# ledpcb.net
KiCad netlist of a schematic drawn in EAGLE
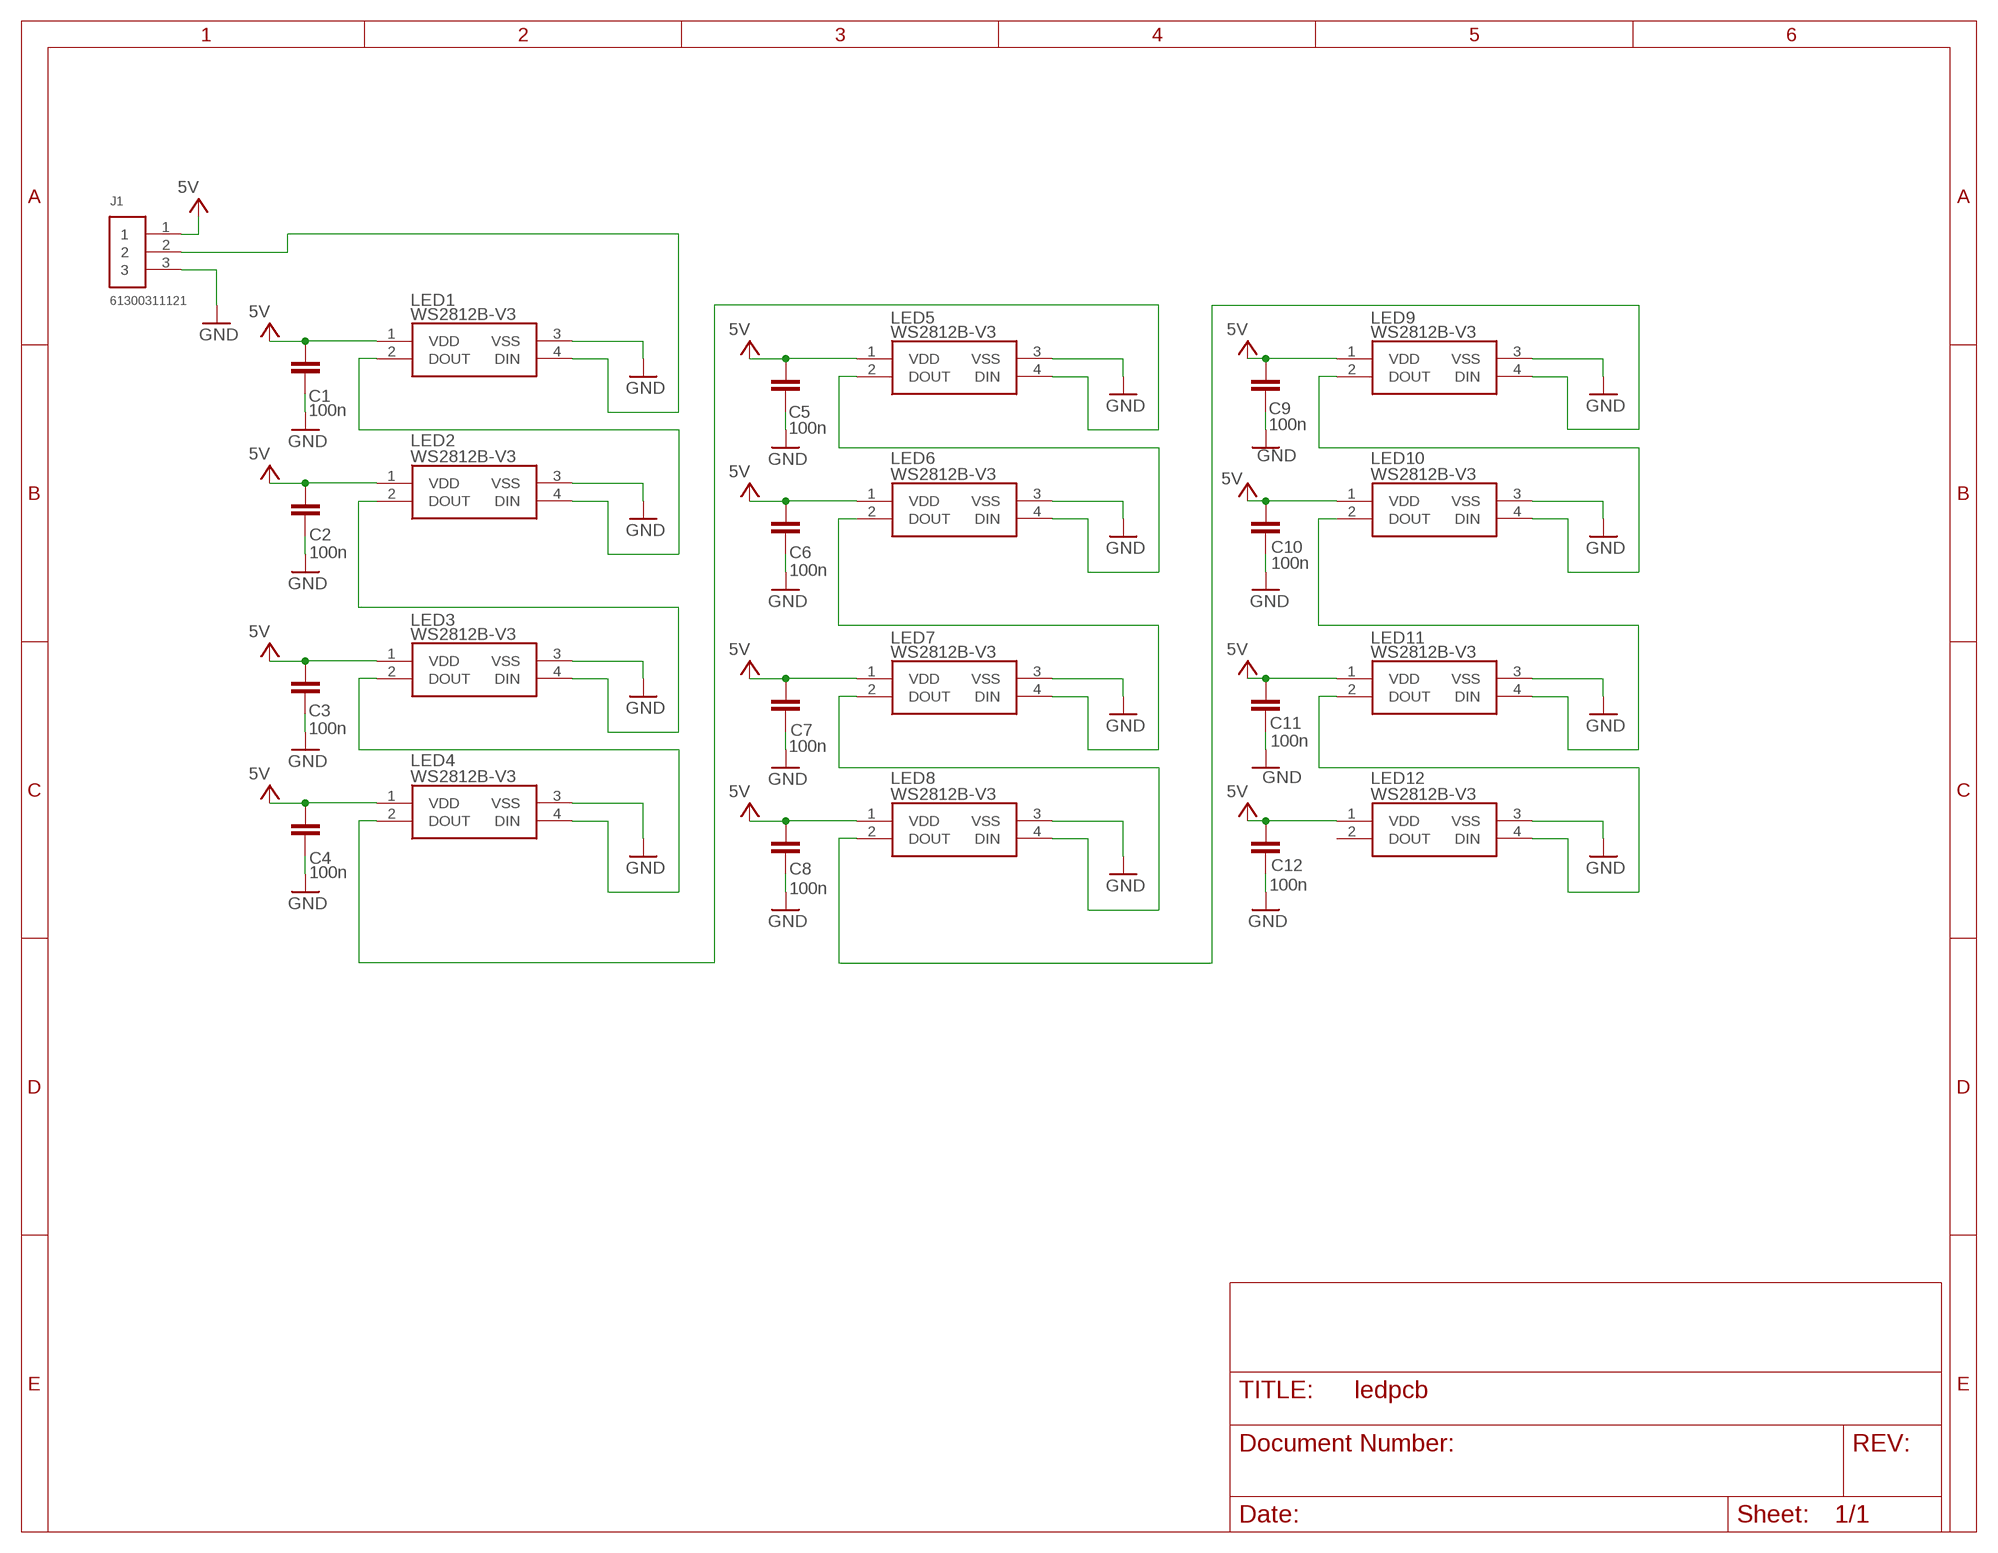
[diagram p0: schematic, sheet 1]

(export (version "E")
  (design (tool "Eeschema 10.0.6"))
  (components
    (comp (ref "C1")
      (value "100n")
      (footprint "eagle-import:C0805")
      (libsource (lib "eagle-import") (part "CAP_SMD0805"))
    )
    (comp (ref "C2")
      (value "100n")
      (footprint "eagle-import:C0805")
      (libsource (lib "eagle-import") (part "CAP_SMD0805"))
    )
    (comp (ref "C3")
      (value "100n")
      (footprint "eagle-import:C0805")
      (libsource (lib "eagle-import") (part "CAP_SMD0805"))
    )
    (comp (ref "C4")
      (value "100n")
      (footprint "eagle-import:C0805")
      (libsource (lib "eagle-import") (part "CAP_SMD0805"))
    )
    (comp (ref "C5")
      (value "100n")
      (footprint "eagle-import:C0805")
      (libsource (lib "eagle-import") (part "CAP_SMD0805"))
    )
    (comp (ref "C6")
      (value "100n")
      (footprint "eagle-import:C0805")
      (libsource (lib "eagle-import") (part "CAP_SMD0805"))
    )
    (comp (ref "C7")
      (value "100n")
      (footprint "eagle-import:C0805")
      (libsource (lib "eagle-import") (part "CAP_SMD0805"))
    )
    (comp (ref "C8")
      (value "100n")
      (footprint "eagle-import:C0805")
      (libsource (lib "eagle-import") (part "CAP_SMD0805"))
    )
    (comp (ref "C9")
      (value "100n")
      (footprint "eagle-import:C0805")
      (libsource (lib "eagle-import") (part "CAP_SMD0805"))
    )
    (comp (ref "C10")
      (value "100n")
      (footprint "eagle-import:C0805")
      (libsource (lib "eagle-import") (part "CAP_SMD0805"))
    )
    (comp (ref "C11")
      (value "100n")
      (footprint "eagle-import:C0805")
      (libsource (lib "eagle-import") (part "CAP_SMD0805"))
    )
    (comp (ref "C12")
      (value "100n")
      (footprint "eagle-import:C0805")
      (libsource (lib "eagle-import") (part "CAP_SMD0805"))
    )
    (comp (ref "J1")
      (value "61300311121")
      (footprint "eagle-import:61300311121")
      (fields
        (field (name "DIGI_KEY_PART_NUMBER") "732-5316-ND")
        (field (name "MANUFACTURER") "Wurth Electronics Inc.")
        (field (name "CREATED_BY") "PCBLayout.com")
      )
      (libsource (lib "eagle-import") (part "61300311121"))
    )
    (comp (ref "LED1")
      (value "WS2812B-V3")
      (footprint "eagle-import:WS2812BV3")
      (libsource (lib "eagle-import") (part "WS2812B-V3"))
    )
    (comp (ref "LED2")
      (value "WS2812B-V3")
      (footprint "eagle-import:WS2812BV3")
      (libsource (lib "eagle-import") (part "WS2812B-V3"))
    )
    (comp (ref "LED3")
      (value "WS2812B-V3")
      (footprint "eagle-import:WS2812BV3")
      (libsource (lib "eagle-import") (part "WS2812B-V3"))
    )
    (comp (ref "LED4")
      (value "WS2812B-V3")
      (footprint "eagle-import:WS2812BV3")
      (libsource (lib "eagle-import") (part "WS2812B-V3"))
    )
    (comp (ref "LED5")
      (value "WS2812B-V3")
      (footprint "eagle-import:WS2812BV3")
      (libsource (lib "eagle-import") (part "WS2812B-V3"))
    )
    (comp (ref "LED6")
      (value "WS2812B-V3")
      (footprint "eagle-import:WS2812BV3")
      (libsource (lib "eagle-import") (part "WS2812B-V3"))
    )
    (comp (ref "LED7")
      (value "WS2812B-V3")
      (footprint "eagle-import:WS2812BV3")
      (libsource (lib "eagle-import") (part "WS2812B-V3"))
    )
    (comp (ref "LED8")
      (value "WS2812B-V3")
      (footprint "eagle-import:WS2812BV3")
      (libsource (lib "eagle-import") (part "WS2812B-V3"))
    )
    (comp (ref "LED9")
      (value "WS2812B-V3")
      (footprint "eagle-import:WS2812BV3")
      (libsource (lib "eagle-import") (part "WS2812B-V3"))
    )
    (comp (ref "LED10")
      (value "WS2812B-V3")
      (footprint "eagle-import:WS2812BV3")
      (libsource (lib "eagle-import") (part "WS2812B-V3"))
    )
    (comp (ref "LED11")
      (value "WS2812B-V3")
      (footprint "eagle-import:WS2812BV3")
      (libsource (lib "eagle-import") (part "WS2812B-V3"))
    )
    (comp (ref "LED12")
      (value "WS2812B-V3")
      (footprint "eagle-import:WS2812BV3")
      (libsource (lib "eagle-import") (part "WS2812B-V3"))
    )
  )
  (nets
    (net (code "1") (name "5V") (class "Default")
      (node (ref "C1") (pin "2") (pinfunction "2_2") (pintype "passive"))
      (node (ref "C10") (pin "1") (pinfunction "1_1") (pintype "passive"))
      (node (ref "C11") (pin "2") (pinfunction "2_2") (pintype "passive"))
      (node (ref "C12") (pin "1") (pinfunction "1_1") (pintype "passive"))
      (node (ref "C2") (pin "1") (pinfunction "1_1") (pintype "passive"))
      (node (ref "C3") (pin "2") (pinfunction "2_2") (pintype "passive"))
      (node (ref "C4") (pin "1") (pinfunction "1_1") (pintype "passive"))
      (node (ref "C5") (pin "2") (pinfunction "2_2") (pintype "passive"))
      (node (ref "C6") (pin "1") (pinfunction "1_1") (pintype "passive"))
      (node (ref "C7") (pin "2") (pinfunction "2_2") (pintype "passive"))
      (node (ref "C8") (pin "1") (pinfunction "1_1") (pintype "passive"))
      (node (ref "C9") (pin "2") (pinfunction "2_2") (pintype "passive"))
      (node (ref "J1") (pin "1") (pinfunction "1_1") (pintype "passive"))
      (node (ref "LED1") (pin "1") (pinfunction "VDD_1") (pintype "bidirectional"))
      (node (ref "LED10") (pin "1") (pinfunction "VDD_1") (pintype "bidirectional"))
      (node (ref "LED11") (pin "1") (pinfunction "VDD_1") (pintype "bidirectional"))
      (node (ref "LED12") (pin "1") (pinfunction "VDD_1") (pintype "bidirectional"))
      (node (ref "LED2") (pin "1") (pinfunction "VDD_1") (pintype "bidirectional"))
      (node (ref "LED3") (pin "1") (pinfunction "VDD_1") (pintype "bidirectional"))
      (node (ref "LED4") (pin "1") (pinfunction "VDD_1") (pintype "bidirectional"))
      (node (ref "LED5") (pin "1") (pinfunction "VDD_1") (pintype "bidirectional"))
      (node (ref "LED6") (pin "1") (pinfunction "VDD_1") (pintype "bidirectional"))
      (node (ref "LED7") (pin "1") (pinfunction "VDD_1") (pintype "bidirectional"))
      (node (ref "LED8") (pin "1") (pinfunction "VDD_1") (pintype "bidirectional"))
      (node (ref "LED9") (pin "1") (pinfunction "VDD_1") (pintype "bidirectional"))
    )
    (net (code "2") (name "GND") (class "Default")
      (node (ref "C1") (pin "1") (pinfunction "1_1") (pintype "passive"))
      (node (ref "C10") (pin "2") (pinfunction "2_2") (pintype "passive"))
      (node (ref "C11") (pin "1") (pinfunction "1_1") (pintype "passive"))
      (node (ref "C12") (pin "2") (pinfunction "2_2") (pintype "passive"))
      (node (ref "C2") (pin "2") (pinfunction "2_2") (pintype "passive"))
      (node (ref "C3") (pin "1") (pinfunction "1_1") (pintype "passive"))
      (node (ref "C4") (pin "2") (pinfunction "2_2") (pintype "passive"))
      (node (ref "C5") (pin "1") (pinfunction "1_1") (pintype "passive"))
      (node (ref "C6") (pin "2") (pinfunction "2_2") (pintype "passive"))
      (node (ref "C7") (pin "1") (pinfunction "1_1") (pintype "passive"))
      (node (ref "C8") (pin "2") (pinfunction "2_2") (pintype "passive"))
      (node (ref "C9") (pin "1") (pinfunction "1_1") (pintype "passive"))
      (node (ref "J1") (pin "3") (pinfunction "3_3") (pintype "passive"))
      (node (ref "LED1") (pin "3") (pinfunction "VSS_3") (pintype "bidirectional"))
      (node (ref "LED10") (pin "3") (pinfunction "VSS_3") (pintype "bidirectional"))
      (node (ref "LED11") (pin "3") (pinfunction "VSS_3") (pintype "bidirectional"))
      (node (ref "LED12") (pin "3") (pinfunction "VSS_3") (pintype "bidirectional"))
      (node (ref "LED2") (pin "3") (pinfunction "VSS_3") (pintype "bidirectional"))
      (node (ref "LED3") (pin "3") (pinfunction "VSS_3") (pintype "bidirectional"))
      (node (ref "LED4") (pin "3") (pinfunction "VSS_3") (pintype "bidirectional"))
      (node (ref "LED5") (pin "3") (pinfunction "VSS_3") (pintype "bidirectional"))
      (node (ref "LED6") (pin "3") (pinfunction "VSS_3") (pintype "bidirectional"))
      (node (ref "LED7") (pin "3") (pinfunction "VSS_3") (pintype "bidirectional"))
      (node (ref "LED8") (pin "3") (pinfunction "VSS_3") (pintype "bidirectional"))
      (node (ref "LED9") (pin "3") (pinfunction "VSS_3") (pintype "bidirectional"))
    )
    (net (code "3") (name "Net-(LED1-DIN)") (class "Default")
      (node (ref "J1") (pin "2") (pinfunction "2_2") (pintype "passive"))
      (node (ref "LED1") (pin "4") (pinfunction "DIN_4") (pintype "bidirectional"))
    )
    (net (code "4") (name "Net-(LED1-DOUT)") (class "Default")
      (node (ref "LED1") (pin "2") (pinfunction "DOUT_2") (pintype "bidirectional"))
      (node (ref "LED2") (pin "4") (pinfunction "DIN_4") (pintype "bidirectional"))
    )
    (net (code "5") (name "Net-(LED2-DOUT)") (class "Default")
      (node (ref "LED2") (pin "2") (pinfunction "DOUT_2") (pintype "bidirectional"))
      (node (ref "LED3") (pin "4") (pinfunction "DIN_4") (pintype "bidirectional"))
    )
    (net (code "6") (name "Net-(LED3-DOUT)") (class "Default")
      (node (ref "LED3") (pin "2") (pinfunction "DOUT_2") (pintype "bidirectional"))
      (node (ref "LED4") (pin "4") (pinfunction "DIN_4") (pintype "bidirectional"))
    )
    (net (code "7") (name "Net-(LED4-DOUT)") (class "Default")
      (node (ref "LED4") (pin "2") (pinfunction "DOUT_2") (pintype "bidirectional"))
      (node (ref "LED5") (pin "4") (pinfunction "DIN_4") (pintype "bidirectional"))
    )
    (net (code "8") (name "Net-(LED5-DOUT)") (class "Default")
      (node (ref "LED5") (pin "2") (pinfunction "DOUT_2") (pintype "bidirectional"))
      (node (ref "LED6") (pin "4") (pinfunction "DIN_4") (pintype "bidirectional"))
    )
    (net (code "9") (name "Net-(LED6-DOUT)") (class "Default")
      (node (ref "LED6") (pin "2") (pinfunction "DOUT_2") (pintype "bidirectional"))
      (node (ref "LED7") (pin "4") (pinfunction "DIN_4") (pintype "bidirectional"))
    )
    (net (code "10") (name "Net-(LED7-DOUT)") (class "Default")
      (node (ref "LED7") (pin "2") (pinfunction "DOUT_2") (pintype "bidirectional"))
      (node (ref "LED8") (pin "4") (pinfunction "DIN_4") (pintype "bidirectional"))
    )
    (net (code "11") (name "Net-(LED8-DOUT)") (class "Default")
      (node (ref "LED8") (pin "2") (pinfunction "DOUT_2") (pintype "bidirectional"))
      (node (ref "LED9") (pin "4") (pinfunction "DIN_4") (pintype "bidirectional"))
    )
    (net (code "12") (name "Net-(LED10-DIN)") (class "Default")
      (node (ref "LED10") (pin "4") (pinfunction "DIN_4") (pintype "bidirectional"))
      (node (ref "LED9") (pin "2") (pinfunction "DOUT_2") (pintype "bidirectional"))
    )
    (net (code "13") (name "Net-(LED10-DOUT)") (class "Default")
      (node (ref "LED10") (pin "2") (pinfunction "DOUT_2") (pintype "bidirectional"))
      (node (ref "LED11") (pin "4") (pinfunction "DIN_4") (pintype "bidirectional"))
    )
    (net (code "14") (name "Net-(LED11-DOUT)") (class "Default")
      (node (ref "LED11") (pin "2") (pinfunction "DOUT_2") (pintype "bidirectional"))
      (node (ref "LED12") (pin "4") (pinfunction "DIN_4") (pintype "bidirectional"))
    )
    (net (code "15") (name "unconnected-(LED12-DOUT-Pad2)") (class "Default")
      (node (ref "LED12") (pin "2") (pinfunction "DOUT_2") (pintype "bidirectional"))
    )
  )
)
